# problem_6.net
KiCad netlist of a schematic drawn in Altium Designer
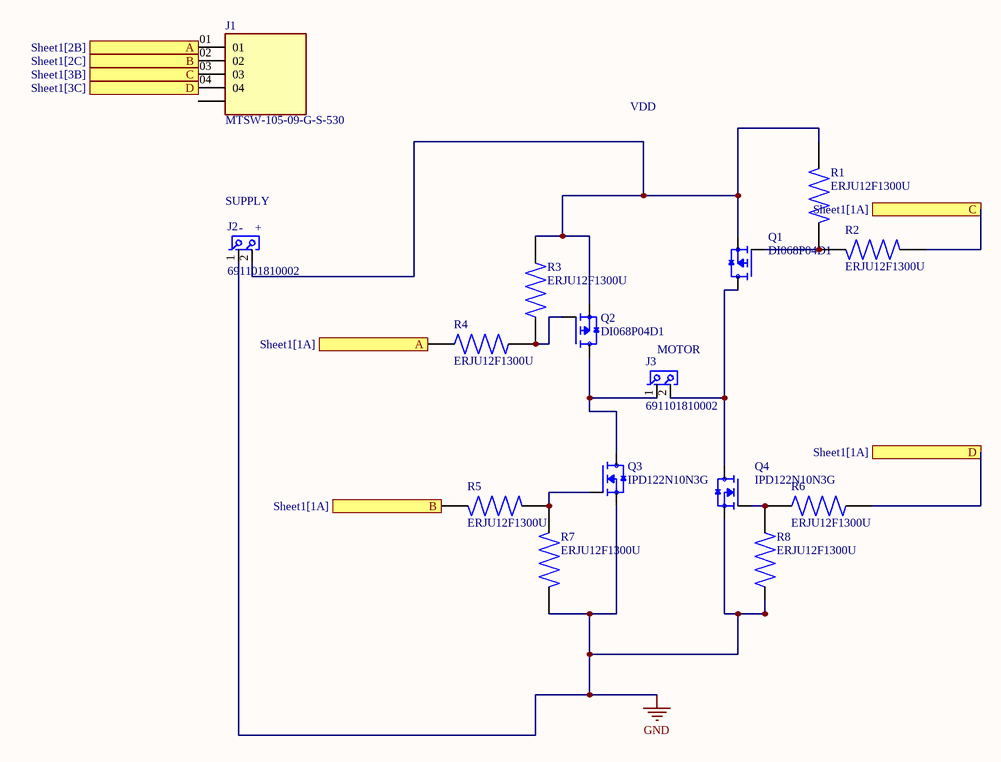
[diagram p0: problem 6.SchDoc]

(export (version "E")
  (design (tool "Eeschema 10.0.6"))
  (components
    (comp (ref "J1")
      (value "MTSW-105-09-G-S-530")
      (footprint "SAMTEC_MTSW-105-09-G-S-530")
      (libsource (lib "MTSW-105-09-G-S-530 (1)") (part "MTSW-105-09-G-S-530"))
    )
    (comp (ref "J2")
      (value "691101810002")
      (footprint "691101810002")
      (fields (field (name "MF") "Wurth Elektronik"))
      (libsource (lib "691101810002") (part "691101810002"))
    )
    (comp (ref "J3")
      (value "691101810002")
      (footprint "691101810002")
      (fields (field (name "MF") "Wurth Elektronik"))
      (libsource (lib "691101810002") (part "691101810002"))
    )
    (comp (ref "Q1")
      (value "DI068P04D1")
      (footprint "TRANS_DI068P04D1")
      (libsource (lib "DI068P04D1") (part "DI068P04D1"))
    )
    (comp (ref "Q2")
      (value "DI068P04D1")
      (footprint "TRANS_DI068P04D1")
      (libsource (lib "DI068P04D1") (part "DI068P04D1"))
    )
    (comp (ref "Q3")
      (value "IPD122N10N3G")
      (footprint "TO252-DPAK")
      (description "MOSFET Transistor, N Channel, 59 A, 100 V, 0.0105 ohm, 10 V, 2.7 V")
      (fields (field (name "MF") "Infineon") (field (name "MP") "IPD122N10N3 G"))
      (libsource (lib "IPD122N10N3G") (part "IPD122N10N3G"))
    )
    (comp (ref "Q4")
      (value "IPD122N10N3G")
      (footprint "TO252-DPAK")
      (description "MOSFET Transistor, N Channel, 59 A, 100 V, 0.0105 ohm, 10 V, 2.7 V")
      (fields (field (name "MF") "Infineon") (field (name "MP") "IPD122N10N3 G"))
      (libsource (lib "IPD122N10N3G") (part "IPD122N10N3G"))
    )
    (comp (ref "R1")
      (value "ERJU12F1300U")
      (footprint "RES_ERJU12F1300U")
      (libsource (lib "ERJU12F1300U") (part "ERJU12F1300U"))
    )
    (comp (ref "R2")
      (value "ERJU12F1300U")
      (footprint "RES_ERJU12F1300U")
      (libsource (lib "ERJU12F1300U") (part "ERJU12F1300U"))
    )
    (comp (ref "R3")
      (value "ERJU12F1300U")
      (footprint "RES_ERJU12F1300U")
      (libsource (lib "ERJU12F1300U") (part "ERJU12F1300U"))
    )
    (comp (ref "R4")
      (value "ERJU12F1300U")
      (footprint "RES_ERJU12F1300U")
      (libsource (lib "ERJU12F1300U") (part "ERJU12F1300U"))
    )
    (comp (ref "R5")
      (value "ERJU12F1300U")
      (footprint "RES_ERJU12F1300U")
      (libsource (lib "ERJU12F1300U") (part "ERJU12F1300U"))
    )
    (comp (ref "R6")
      (value "ERJU12F1300U")
      (footprint "RES_ERJU12F1300U")
      (libsource (lib "ERJU12F1300U") (part "ERJU12F1300U"))
    )
    (comp (ref "R7")
      (value "ERJU12F1300U")
      (footprint "RES_ERJU12F1300U")
      (libsource (lib "ERJU12F1300U") (part "ERJU12F1300U"))
    )
    (comp (ref "R8")
      (value "ERJU12F1300U")
      (footprint "RES_ERJU12F1300U")
      (libsource (lib "ERJU12F1300U") (part "ERJU12F1300U"))
    )
  )
  (nets
    (net (code "1") (name "/A") (class "Default")
      (node (ref "J1") (pin "01") (pinfunction "01_01") (pintype "passive"))
      (node (ref "R4") (pin "1") (pinfunction "1_1") (pintype "passive"))
    )
    (net (code "2") (name "/B") (class "Default")
      (node (ref "J1") (pin "02") (pinfunction "02_02") (pintype "passive"))
      (node (ref "R5") (pin "1") (pinfunction "1_1") (pintype "passive"))
    )
    (net (code "3") (name "/C") (class "Default")
      (node (ref "J1") (pin "03") (pinfunction "03_03") (pintype "passive"))
      (node (ref "R2") (pin "1") (pinfunction "1_1") (pintype "passive"))
    )
    (net (code "4") (name "/D") (class "Default")
      (node (ref "J1") (pin "04") (pinfunction "04_04") (pintype "passive"))
      (node (ref "R6") (pin "1") (pinfunction "1_1") (pintype "passive"))
    )
    (net (code "5") (name "GND") (class "Default")
      (node (ref "J2") (pin "1") (pinfunction "1_1") (pintype "passive"))
      (node (ref "Q3") (pin "3") (pinfunction "S_3") (pintype "passive"))
      (node (ref "Q4") (pin "3") (pinfunction "S_3") (pintype "passive"))
      (node (ref "R7") (pin "2") (pinfunction "2_2") (pintype "passive"))
      (node (ref "R8") (pin "2") (pinfunction "2_2") (pintype "passive"))
    )
    (net (code "6") (name "Net-(Q1-D)") (class "Default")
      (node (ref "J3") (pin "2") (pinfunction "2_2") (pintype "passive"))
      (node (ref "Q1") (pin "4") (pinfunction "D_4") (pintype "passive"))
      (node (ref "Q4") (pin "2") (pinfunction "D_2") (pintype "passive"))
    )
    (net (code "7") (name "Net-(Q1-G)") (class "Default")
      (node (ref "Q1") (pin "1") (pinfunction "G_1") (pintype "passive"))
      (node (ref "R1") (pin "1") (pinfunction "1_1") (pintype "passive"))
      (node (ref "R2") (pin "2") (pinfunction "2_2") (pintype "passive"))
    )
    (net (code "8") (name "Net-(Q1-S)") (class "Default")
      (node (ref "J2") (pin "2") (pinfunction "2_2") (pintype "passive"))
      (node (ref "Q1") (pin "3") (pinfunction "S_3") (pintype "passive"))
      (node (ref "Q2") (pin "3") (pinfunction "S_3") (pintype "passive"))
      (node (ref "R1") (pin "2") (pinfunction "2_2") (pintype "passive"))
      (node (ref "R3") (pin "2") (pinfunction "2_2") (pintype "passive"))
    )
    (net (code "9") (name "Net-(Q2-D)") (class "Default")
      (node (ref "J3") (pin "1") (pinfunction "1_1") (pintype "passive"))
      (node (ref "Q2") (pin "4") (pinfunction "D_4") (pintype "passive"))
      (node (ref "Q3") (pin "2") (pinfunction "D_2") (pintype "passive"))
    )
    (net (code "10") (name "Net-(Q2-G)") (class "Default")
      (node (ref "Q2") (pin "1") (pinfunction "G_1") (pintype "passive"))
      (node (ref "R3") (pin "1") (pinfunction "1_1") (pintype "passive"))
      (node (ref "R4") (pin "2") (pinfunction "2_2") (pintype "passive"))
    )
    (net (code "11") (name "Net-(Q3-G)") (class "Default")
      (node (ref "Q3") (pin "1") (pinfunction "G_1") (pintype "passive"))
      (node (ref "R5") (pin "2") (pinfunction "2_2") (pintype "passive"))
      (node (ref "R7") (pin "1") (pinfunction "1_1") (pintype "passive"))
    )
    (net (code "12") (name "Net-(Q4-G)") (class "Default")
      (node (ref "Q4") (pin "1") (pinfunction "G_1") (pintype "passive"))
      (node (ref "R6") (pin "2") (pinfunction "2_2") (pintype "passive"))
      (node (ref "R8") (pin "1") (pinfunction "1_1") (pintype "passive"))
    )
    (net (code "13") (name "unconnected-(J1-Pad05)") (class "Default")
      (node (ref "J1") (pin "05") (pinfunction "05_05") (pintype "passive"))
    )
  )
)
